# hoop.net
KiCad netlist of a schematic drawn in EAGLE
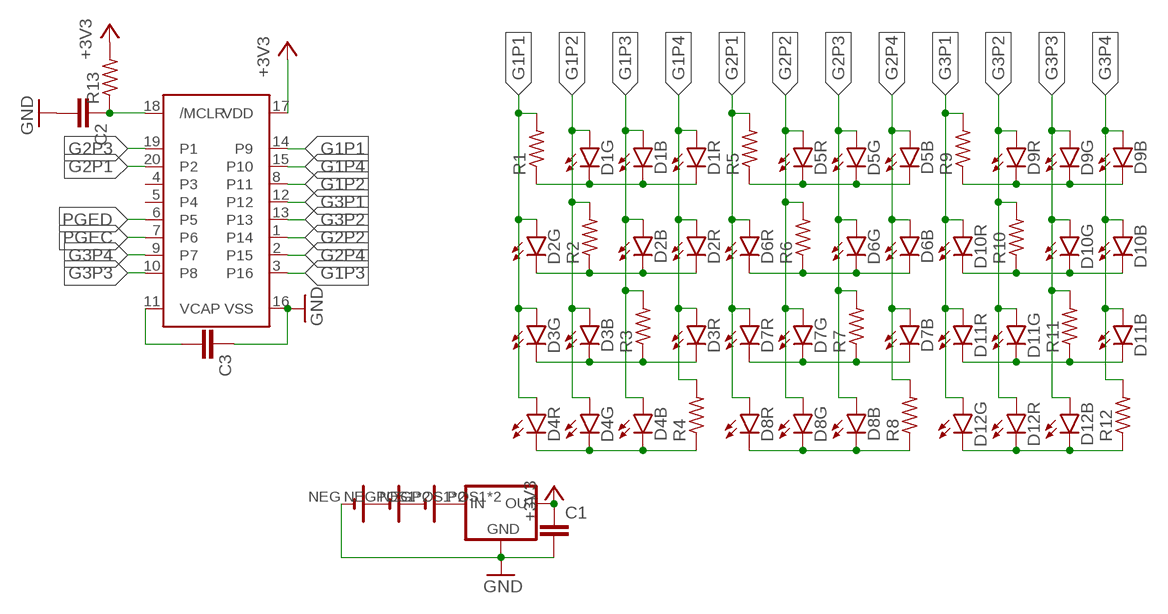
[diagram p0: schematic, sheet 1]

(export (version "E")
  (design (tool "Eeschema 10.0.6"))
  (components
    (comp (ref "B1")
      (value "P312")
      (footprint "eagle-import:P312_CLIP")
      (libsource (lib "eagle-import") (part "P312"))
    )
    (comp (ref "B2")
      (value "P312")
      (footprint "eagle-import:P312_CLIP")
      (libsource (lib "eagle-import") (part "P312"))
    )
    (comp (ref "B3")
      (value "P312")
      (footprint "eagle-import:P312_CLIP")
      (libsource (lib "eagle-import") (part "P312"))
    )
    (comp (ref "C1")
      (value "C-EUC0402")
      (footprint "eagle-import:C0402")
      (libsource (lib "eagle-import") (part "C-EUC0402"))
    )
    (comp (ref "C2")
      (value "C-EUC0402")
      (footprint "eagle-import:C0402")
      (libsource (lib "eagle-import") (part "C-EUC0402"))
    )
    (comp (ref "C3")
      (value "C-EUC0402")
      (footprint "eagle-import:C0402")
      (libsource (lib "eagle-import") (part "C-EUC0402"))
    )
    (comp (ref "D1")
      (value "FM-Z2727RGBA-SH")
      (footprint "eagle-import:SMD_2.8X2.7MM")
      (libsource (lib "eagle-import") (part "FM-Z2727RGBA-SH"))
    )
    (comp (ref "D2")
      (value "FM-Z2727RGBA-SH")
      (footprint "eagle-import:SMD_2.8X2.7MM")
      (libsource (lib "eagle-import") (part "FM-Z2727RGBA-SH"))
    )
    (comp (ref "D3")
      (value "FM-Z2727RGBA-SH")
      (footprint "eagle-import:SMD_2.8X2.7MM")
      (libsource (lib "eagle-import") (part "FM-Z2727RGBA-SH"))
    )
    (comp (ref "D4")
      (value "FM-Z2727RGBA-SH")
      (footprint "eagle-import:SMD_2.8X2.7MM")
      (libsource (lib "eagle-import") (part "FM-Z2727RGBA-SH"))
    )
    (comp (ref "D5")
      (value "FM-Z2727RGBA-SH")
      (footprint "eagle-import:SMD_2.8X2.7MM")
      (libsource (lib "eagle-import") (part "FM-Z2727RGBA-SH"))
    )
    (comp (ref "D6")
      (value "FM-Z2727RGBA-SH")
      (footprint "eagle-import:SMD_2.8X2.7MM")
      (libsource (lib "eagle-import") (part "FM-Z2727RGBA-SH"))
    )
    (comp (ref "D7")
      (value "FM-Z2727RGBA-SH")
      (footprint "eagle-import:SMD_2.8X2.7MM")
      (libsource (lib "eagle-import") (part "FM-Z2727RGBA-SH"))
    )
    (comp (ref "D8")
      (value "FM-Z2727RGBA-SH")
      (footprint "eagle-import:SMD_2.8X2.7MM")
      (libsource (lib "eagle-import") (part "FM-Z2727RGBA-SH"))
    )
    (comp (ref "D9")
      (value "FM-Z2727RGBA-SH")
      (footprint "eagle-import:SMD_2.8X2.7MM")
      (libsource (lib "eagle-import") (part "FM-Z2727RGBA-SH"))
    )
    (comp (ref "D10")
      (value "FM-Z2727RGBA-SH")
      (footprint "eagle-import:SMD_2.8X2.7MM")
      (libsource (lib "eagle-import") (part "FM-Z2727RGBA-SH"))
    )
    (comp (ref "D11")
      (value "FM-Z2727RGBA-SH")
      (footprint "eagle-import:SMD_2.8X2.7MM")
      (libsource (lib "eagle-import") (part "FM-Z2727RGBA-SH"))
    )
    (comp (ref "D12")
      (value "FM-Z2727RGBA-SH")
      (footprint "eagle-import:SMD_2.8X2.7MM")
      (libsource (lib "eagle-import") (part "FM-Z2727RGBA-SH"))
    )
    (comp (ref "R1")
      (value "R-US_R0805")
      (footprint "eagle-import:R0805")
      (libsource (lib "eagle-import") (part "R-US_R0805"))
    )
    (comp (ref "R2")
      (value "R-US_R0805")
      (footprint "eagle-import:R0805")
      (libsource (lib "eagle-import") (part "R-US_R0805"))
    )
    (comp (ref "R3")
      (value "R-US_R0805")
      (footprint "eagle-import:R0805")
      (libsource (lib "eagle-import") (part "R-US_R0805"))
    )
    (comp (ref "R4")
      (value "R-US_R0805")
      (footprint "eagle-import:R0805")
      (libsource (lib "eagle-import") (part "R-US_R0805"))
    )
    (comp (ref "R5")
      (value "R-US_R0805")
      (footprint "eagle-import:R0805")
      (libsource (lib "eagle-import") (part "R-US_R0805"))
    )
    (comp (ref "R6")
      (value "R-US_R0805")
      (footprint "eagle-import:R0805")
      (libsource (lib "eagle-import") (part "R-US_R0805"))
    )
    (comp (ref "R7")
      (value "R-US_R0805")
      (footprint "eagle-import:R0805")
      (libsource (lib "eagle-import") (part "R-US_R0805"))
    )
    (comp (ref "R8")
      (value "R-US_R0805")
      (footprint "eagle-import:R0805")
      (libsource (lib "eagle-import") (part "R-US_R0805"))
    )
    (comp (ref "R9")
      (value "R-US_R0805")
      (footprint "eagle-import:R0805")
      (libsource (lib "eagle-import") (part "R-US_R0805"))
    )
    (comp (ref "R10")
      (value "R-US_R0805")
      (footprint "eagle-import:R0805")
      (libsource (lib "eagle-import") (part "R-US_R0805"))
    )
    (comp (ref "R11")
      (value "R-US_R0805")
      (footprint "eagle-import:R0805")
      (libsource (lib "eagle-import") (part "R-US_R0805"))
    )
    (comp (ref "R12")
      (value "R-US_R0805")
      (footprint "eagle-import:R0805")
      (libsource (lib "eagle-import") (part "R-US_R0805"))
    )
    (comp (ref "R13")
      (value "R-US_R0402")
      (footprint "eagle-import:R0402")
      (libsource (lib "eagle-import") (part "R-US_R0402"))
    )
    (comp (ref "U1")
      (value "PIC32MM0064GPL020-I/ML")
      (footprint "eagle-import:QFN50P400X400X100-21T280N")
      (libsource (lib "eagle-import") (part "PIC32MM0064GPL020-I/ML"))
    )
    (comp (ref "U2")
      (value "SGM2200")
      (footprint "eagle-import:SOT23")
      (libsource (lib "eagle-import") (part "SGM2200"))
    )
  )
  (nets
    (net (code "1") (name "+3V3") (class "Default")
      (node (ref "C1") (pin "1") (pinfunction "1_1") (pintype "passive"))
      (node (ref "R13") (pin "2") (pinfunction "2_2") (pintype "passive"))
      (node (ref "U1") (pin "17") (pinfunction "VDD_17") (pintype "bidirectional"))
      (node (ref "U2") (pin "2") (pinfunction "OUT_2") (pintype "passive"))
    )
    (net (code "2") (name "G1P1") (class "Default")
      (node (ref "D2") (pin "G+") (pinfunction "A_G+") (pintype "passive"))
      (node (ref "D3") (pin "G+") (pinfunction "A_G+") (pintype "passive"))
      (node (ref "D4") (pin "R+") (pinfunction "A_R+") (pintype "passive"))
      (node (ref "R1") (pin "2") (pinfunction "2_2") (pintype "passive"))
      (node (ref "U1") (pin "14") (pinfunction "P9_14") (pintype "bidirectional"))
    )
    (net (code "3") (name "G1P2") (class "Default")
      (node (ref "D1") (pin "G+") (pinfunction "A_G+") (pintype "passive"))
      (node (ref "D3") (pin "B+") (pinfunction "A_B+") (pintype "passive"))
      (node (ref "D4") (pin "G+") (pinfunction "A_G+") (pintype "passive"))
      (node (ref "R2") (pin "2") (pinfunction "2_2") (pintype "passive"))
      (node (ref "U1") (pin "8") (pinfunction "P11_8") (pintype "bidirectional"))
    )
    (net (code "4") (name "G1P3") (class "Default")
      (node (ref "D1") (pin "B+") (pinfunction "A_B+") (pintype "passive"))
      (node (ref "D2") (pin "B+") (pinfunction "A_B+") (pintype "passive"))
      (node (ref "D4") (pin "B+") (pinfunction "A_B+") (pintype "passive"))
      (node (ref "R3") (pin "2") (pinfunction "2_2") (pintype "passive"))
      (node (ref "U1") (pin "3") (pinfunction "P16_3") (pintype "bidirectional"))
    )
    (net (code "5") (name "G1P4") (class "Default")
      (node (ref "D1") (pin "R+") (pinfunction "A_R+") (pintype "passive"))
      (node (ref "D2") (pin "R+") (pinfunction "A_R+") (pintype "passive"))
      (node (ref "D3") (pin "R+") (pinfunction "A_R+") (pintype "passive"))
      (node (ref "R4") (pin "2") (pinfunction "2_2") (pintype "passive"))
      (node (ref "U1") (pin "15") (pinfunction "P10_15") (pintype "bidirectional"))
    )
    (net (code "6") (name "G2P1") (class "Default")
      (node (ref "D6") (pin "R+") (pinfunction "A_R+") (pintype "passive"))
      (node (ref "D7") (pin "R+") (pinfunction "A_R+") (pintype "passive"))
      (node (ref "D8") (pin "R+") (pinfunction "A_R+") (pintype "passive"))
      (node (ref "R5") (pin "2") (pinfunction "2_2") (pintype "passive"))
      (node (ref "U1") (pin "20") (pinfunction "P2_20") (pintype "bidirectional"))
    )
    (net (code "7") (name "G2P2") (class "Default")
      (node (ref "D5") (pin "R+") (pinfunction "A_R+") (pintype "passive"))
      (node (ref "D7") (pin "G+") (pinfunction "A_G+") (pintype "passive"))
      (node (ref "D8") (pin "G+") (pinfunction "A_G+") (pintype "passive"))
      (node (ref "R6") (pin "2") (pinfunction "2_2") (pintype "passive"))
      (node (ref "U1") (pin "1") (pinfunction "P14_1") (pintype "bidirectional"))
    )
    (net (code "8") (name "G2P3") (class "Default")
      (node (ref "D5") (pin "G+") (pinfunction "A_G+") (pintype "passive"))
      (node (ref "D6") (pin "G+") (pinfunction "A_G+") (pintype "passive"))
      (node (ref "D8") (pin "B+") (pinfunction "A_B+") (pintype "passive"))
      (node (ref "R7") (pin "2") (pinfunction "2_2") (pintype "passive"))
      (node (ref "U1") (pin "19") (pinfunction "P1_19") (pintype "bidirectional"))
    )
    (net (code "9") (name "G2P4") (class "Default")
      (node (ref "D5") (pin "B+") (pinfunction "A_B+") (pintype "passive"))
      (node (ref "D6") (pin "B+") (pinfunction "A_B+") (pintype "passive"))
      (node (ref "D7") (pin "B+") (pinfunction "A_B+") (pintype "passive"))
      (node (ref "R8") (pin "2") (pinfunction "2_2") (pintype "passive"))
      (node (ref "U1") (pin "2") (pinfunction "P15_2") (pintype "bidirectional"))
    )
    (net (code "10") (name "G3P1") (class "Default")
      (node (ref "D10") (pin "R+") (pinfunction "A_R+") (pintype "passive"))
      (node (ref "D11") (pin "R+") (pinfunction "A_R+") (pintype "passive"))
      (node (ref "D12") (pin "G+") (pinfunction "A_G+") (pintype "passive"))
      (node (ref "R9") (pin "2") (pinfunction "2_2") (pintype "passive"))
      (node (ref "U1") (pin "12") (pinfunction "P12_12") (pintype "bidirectional"))
    )
    (net (code "11") (name "G3P2") (class "Default")
      (node (ref "D11") (pin "G+") (pinfunction "A_G+") (pintype "passive"))
      (node (ref "D12") (pin "R+") (pinfunction "A_R+") (pintype "passive"))
      (node (ref "D9") (pin "R+") (pinfunction "A_R+") (pintype "passive"))
      (node (ref "R10") (pin "2") (pinfunction "2_2") (pintype "passive"))
      (node (ref "U1") (pin "13") (pinfunction "P13_13") (pintype "bidirectional"))
    )
    (net (code "12") (name "G3P3") (class "Default")
      (node (ref "D10") (pin "G+") (pinfunction "A_G+") (pintype "passive"))
      (node (ref "D12") (pin "B+") (pinfunction "A_B+") (pintype "passive"))
      (node (ref "D9") (pin "G+") (pinfunction "A_G+") (pintype "passive"))
      (node (ref "R11") (pin "2") (pinfunction "2_2") (pintype "passive"))
      (node (ref "U1") (pin "10") (pinfunction "P8_10") (pintype "bidirectional"))
    )
    (net (code "13") (name "G3P4") (class "Default")
      (node (ref "D10") (pin "B+") (pinfunction "A_B+") (pintype "passive"))
      (node (ref "D11") (pin "B+") (pinfunction "A_B+") (pintype "passive"))
      (node (ref "D9") (pin "B+") (pinfunction "A_B+") (pintype "passive"))
      (node (ref "R12") (pin "2") (pinfunction "2_2") (pintype "passive"))
      (node (ref "U1") (pin "9") (pinfunction "P7_9") (pintype "bidirectional"))
    )
    (net (code "14") (name "GND") (class "Default")
      (node (ref "B1") (pin "NEG") (pinfunction "-_NEG") (pintype "passive"))
      (node (ref "C1") (pin "2") (pinfunction "2_2") (pintype "passive"))
      (node (ref "C2") (pin "2") (pinfunction "2_2") (pintype "passive"))
      (node (ref "C3") (pin "1") (pinfunction "1_1") (pintype "passive"))
      (node (ref "U1") (pin "16") (pinfunction "VSS_16") (pintype "bidirectional"))
      (node (ref "U2") (pin "1") (pinfunction "GND_1") (pintype "input"))
    )
    (net (code "15") (name "Net-(B2--)") (class "Default")
      (node (ref "B1") (pin "POS1") (pinfunction "+_POS1") (pintype "passive"))
      (node (ref "B1") (pin "POS2") (pinfunction "+_POS2") (pintype "passive"))
      (node (ref "B2") (pin "NEG") (pinfunction "-_NEG") (pintype "passive"))
    )
    (net (code "16") (name "Net-(B3--)") (class "Default")
      (node (ref "B2") (pin "POS1") (pinfunction "+_POS1") (pintype "passive"))
      (node (ref "B2") (pin "POS2") (pinfunction "+_POS2") (pintype "passive"))
      (node (ref "B3") (pin "NEG") (pinfunction "-_NEG") (pintype "passive"))
    )
    (net (code "17") (name "Net-(D1A-C)") (class "Default")
      (node (ref "D1") (pin "B-") (pinfunction "C_B-") (pintype "passive"))
      (node (ref "D1") (pin "G-") (pinfunction "C_G-") (pintype "passive"))
      (node (ref "D1") (pin "R-") (pinfunction "C_R-") (pintype "passive"))
      (node (ref "R1") (pin "1") (pinfunction "1_1") (pintype "passive"))
    )
    (net (code "18") (name "Net-(D2A-C)") (class "Default")
      (node (ref "D2") (pin "B-") (pinfunction "C_B-") (pintype "passive"))
      (node (ref "D2") (pin "G-") (pinfunction "C_G-") (pintype "passive"))
      (node (ref "D2") (pin "R-") (pinfunction "C_R-") (pintype "passive"))
      (node (ref "R2") (pin "1") (pinfunction "1_1") (pintype "passive"))
    )
    (net (code "19") (name "Net-(D3A-C)") (class "Default")
      (node (ref "D3") (pin "B-") (pinfunction "C_B-") (pintype "passive"))
      (node (ref "D3") (pin "G-") (pinfunction "C_G-") (pintype "passive"))
      (node (ref "D3") (pin "R-") (pinfunction "C_R-") (pintype "passive"))
      (node (ref "R3") (pin "1") (pinfunction "1_1") (pintype "passive"))
    )
    (net (code "20") (name "Net-(D4A-C)") (class "Default")
      (node (ref "D4") (pin "B-") (pinfunction "C_B-") (pintype "passive"))
      (node (ref "D4") (pin "G-") (pinfunction "C_G-") (pintype "passive"))
      (node (ref "D4") (pin "R-") (pinfunction "C_R-") (pintype "passive"))
      (node (ref "R4") (pin "1") (pinfunction "1_1") (pintype "passive"))
    )
    (net (code "21") (name "Net-(D5A-C)") (class "Default")
      (node (ref "D5") (pin "B-") (pinfunction "C_B-") (pintype "passive"))
      (node (ref "D5") (pin "G-") (pinfunction "C_G-") (pintype "passive"))
      (node (ref "D5") (pin "R-") (pinfunction "C_R-") (pintype "passive"))
      (node (ref "R5") (pin "1") (pinfunction "1_1") (pintype "passive"))
    )
    (net (code "22") (name "Net-(D6A-C)") (class "Default")
      (node (ref "D6") (pin "B-") (pinfunction "C_B-") (pintype "passive"))
      (node (ref "D6") (pin "G-") (pinfunction "C_G-") (pintype "passive"))
      (node (ref "D6") (pin "R-") (pinfunction "C_R-") (pintype "passive"))
      (node (ref "R6") (pin "1") (pinfunction "1_1") (pintype "passive"))
    )
    (net (code "23") (name "Net-(D7A-C)") (class "Default")
      (node (ref "D7") (pin "B-") (pinfunction "C_B-") (pintype "passive"))
      (node (ref "D7") (pin "G-") (pinfunction "C_G-") (pintype "passive"))
      (node (ref "D7") (pin "R-") (pinfunction "C_R-") (pintype "passive"))
      (node (ref "R7") (pin "1") (pinfunction "1_1") (pintype "passive"))
    )
    (net (code "24") (name "Net-(D8A-C)") (class "Default")
      (node (ref "D8") (pin "B-") (pinfunction "C_B-") (pintype "passive"))
      (node (ref "D8") (pin "G-") (pinfunction "C_G-") (pintype "passive"))
      (node (ref "D8") (pin "R-") (pinfunction "C_R-") (pintype "passive"))
      (node (ref "R8") (pin "1") (pinfunction "1_1") (pintype "passive"))
    )
    (net (code "25") (name "Net-(D9A-C)") (class "Default")
      (node (ref "D9") (pin "B-") (pinfunction "C_B-") (pintype "passive"))
      (node (ref "D9") (pin "G-") (pinfunction "C_G-") (pintype "passive"))
      (node (ref "D9") (pin "R-") (pinfunction "C_R-") (pintype "passive"))
      (node (ref "R9") (pin "1") (pinfunction "1_1") (pintype "passive"))
    )
    (net (code "26") (name "Net-(D10A-C)") (class "Default")
      (node (ref "D10") (pin "B-") (pinfunction "C_B-") (pintype "passive"))
      (node (ref "D10") (pin "G-") (pinfunction "C_G-") (pintype "passive"))
      (node (ref "D10") (pin "R-") (pinfunction "C_R-") (pintype "passive"))
      (node (ref "R10") (pin "1") (pinfunction "1_1") (pintype "passive"))
    )
    (net (code "27") (name "Net-(D11A-C)") (class "Default")
      (node (ref "D11") (pin "B-") (pinfunction "C_B-") (pintype "passive"))
      (node (ref "D11") (pin "G-") (pinfunction "C_G-") (pintype "passive"))
      (node (ref "D11") (pin "R-") (pinfunction "C_R-") (pintype "passive"))
      (node (ref "R11") (pin "1") (pinfunction "1_1") (pintype "passive"))
    )
    (net (code "28") (name "Net-(D12A-C)") (class "Default")
      (node (ref "D12") (pin "B-") (pinfunction "C_B-") (pintype "passive"))
      (node (ref "D12") (pin "G-") (pinfunction "C_G-") (pintype "passive"))
      (node (ref "D12") (pin "R-") (pinfunction "C_R-") (pintype "passive"))
      (node (ref "R12") (pin "1") (pinfunction "1_1") (pintype "passive"))
    )
    (net (code "29") (name "Net-(U1-VCAP)") (class "Default")
      (node (ref "C3") (pin "2") (pinfunction "2_2") (pintype "passive"))
      (node (ref "U1") (pin "11") (pinfunction "VCAP_11") (pintype "bidirectional"))
    )
    (net (code "30") (name "Net-(U1-{slash}MCLR)") (class "Default")
      (node (ref "C2") (pin "1") (pinfunction "1_1") (pintype "passive"))
      (node (ref "R13") (pin "1") (pinfunction "1_1") (pintype "passive"))
      (node (ref "U1") (pin "18") (pinfunction "/MCLR_18") (pintype "bidirectional"))
    )
    (net (code "31") (name "Net-(U2-IN)") (class "Default")
      (node (ref "B3") (pin "POS1") (pinfunction "+_POS1") (pintype "passive"))
      (node (ref "B3") (pin "POS2") (pinfunction "+_POS2") (pintype "passive"))
      (node (ref "U2") (pin "3") (pinfunction "IN_3") (pintype "input"))
    )
    (net (code "32") (name "PGEC") (class "Default")
      (node (ref "U1") (pin "7") (pinfunction "P6_7") (pintype "bidirectional"))
    )
    (net (code "33") (name "PGED") (class "Default")
      (node (ref "U1") (pin "6") (pinfunction "P5_6") (pintype "bidirectional"))
    )
    (net (code "34") (name "unconnected-(U1-P3-Pad4)") (class "Default")
      (node (ref "U1") (pin "4") (pinfunction "P3_4") (pintype "bidirectional"))
    )
    (net (code "35") (name "unconnected-(U1-P4-Pad5)") (class "Default")
      (node (ref "U1") (pin "5") (pinfunction "P4_5") (pintype "bidirectional"))
    )
  )
)
